# RoBeast_uC.net
KiCad netlist of a schematic drawn in Altium Designer
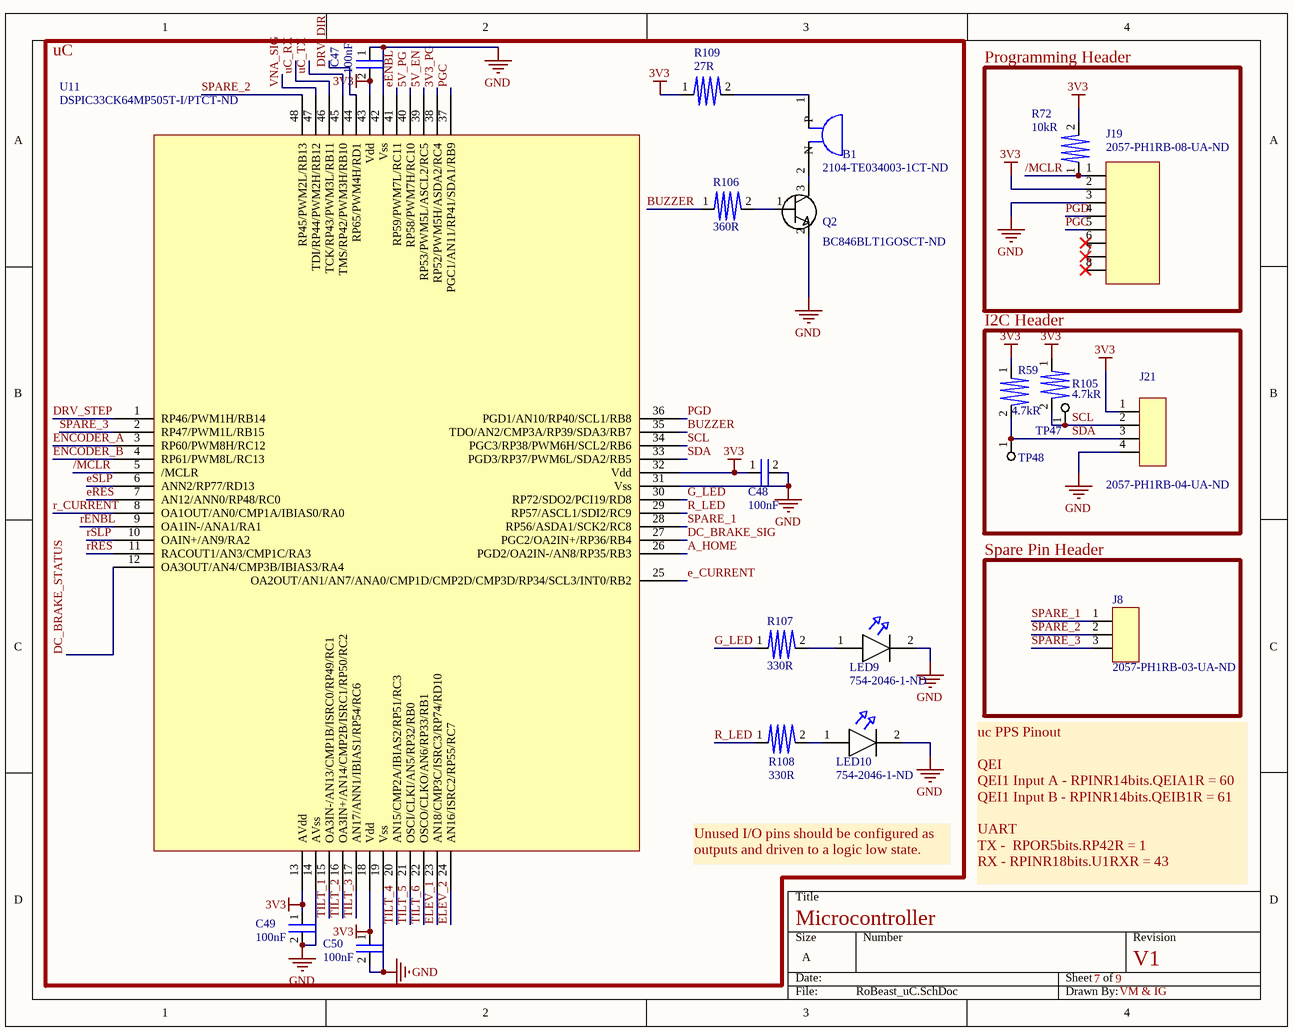
[diagram p0: RoBeast_uC.SchDoc]

(export (version "E")
  (design (tool "Eeschema 10.0.6"))
  (components
    (comp (ref "B1")
      (value "Buzzer")
      (footprint "TE034003-1")
      (description "Electro-mechanical Transducer")
      (fields
        (field (name "MANUFACTURER") "DB Unlimited")
        (field (name "MANUFACTURER PART NUMBER") "TE034003-1")
        (field (name "SUPPLIER PART NUMBER 1") "2104-TE034003-1CT-ND")
      )
      (libsource (lib "RoBeast_Schematic_Library") (part "TE034003-1"))
    )
    (comp (ref "C47")
      (value "100nF")
      (footprint "0805")
      (fields
        (field (name "MANUFACTURER") "KEMET")
        (field (name "MANUFACTURER PART NUMBER") "C0805C104J5RACTU")
      )
      (libsource (lib "RoBeast_Schematic_Library") (part "C0805C104J5RAC7800"))
    )
    (comp (ref "C48")
      (value "100nF")
      (footprint "0805")
      (fields
        (field (name "MANUFACTURER") "KEMET")
        (field (name "MANUFACTURER PART NUMBER") "C0805C104J5RACTU")
      )
      (libsource (lib "RoBeast_Schematic_Library") (part "C0805C104J5RAC7800"))
    )
    (comp (ref "C49")
      (value "100nF")
      (footprint "0805")
      (fields
        (field (name "MANUFACTURER") "KEMET")
        (field (name "MANUFACTURER PART NUMBER") "C0805C104J5RACTU")
      )
      (libsource (lib "RoBeast_Schematic_Library") (part "C0805C104J5RAC7800"))
    )
    (comp (ref "C50")
      (value "100nF")
      (footprint "0805")
      (fields
        (field (name "MANUFACTURER") "KEMET")
        (field (name "MANUFACTURER PART NUMBER") "C0805C104J5RACTU")
      )
      (libsource (lib "RoBeast_Schematic_Library") (part "C0805C104J5RAC7800"))
    )
    (comp (ref "J8")
      (value "3 Pin Connector")
      (footprint "PH1RB-03-UA")
      (description "Conn Unshrouded Header HDR 3 POS 2.54mm Solder RA Side Entry Thru-Hole")
      (fields
        (field (name "MANUFACTURER") "Adam Equipment")
        (field (name "MANUFACTURER PART NUMBER") "PH1RB-03-UA")
        (field (name "SUPPLIER PART NUMBER") "2057-PH1RB-03-UA-ND")
      )
      (libsource (lib "RoBeast_Schematic_Library") (part "PH1RB-03-UA"))
    )
    (comp (ref "J19")
      (value "8 Pin Connector")
      (footprint "PH1RB-08-UA")
      (description "Conn Unshrouded Header HDR 8 POS 2.54mm Solder RA Thru-Hole")
      (fields
        (field (name "MANUFACTURER") "Adam Equipment")
        (field (name "MANUFACTURER PART NUMBER") "PH1RB-08-UA")
        (field (name "SUPPLIER PART NUMBER 1") "2057-PH1RB-08-UA-ND")
      )
      (libsource (lib "RoBeast_Schematic_Library") (part "PH1RB-08-UA"))
    )
    (comp (ref "J21")
      (value "4 Pin Connector")
      (footprint "PH1RB-04-UA")
      (description "Conn Unshrouded Header HDR 4 POS 2.54mm Solder RA Thru-Hole")
      (fields
        (field (name "MANUFACTURER") "Adam Equipment")
        (field (name "MANUFACTURER PART NUMBER") "PH1RB-04-UA")
        (field (name "SUPPLIER PART NUMBER") "2057-PH1RB-04-UA-ND")
      )
      (libsource (lib "RoBeast_Schematic_Library") (part "PH1RB-04-UA"))
    )
    (comp (ref "LED9")
      (value "Blue LED")
      (footprint "0805_LED")
      (description "Single Color LED")
      (fields
        (field (name "MANUFACTURER") "Kingbright")
        (field (name "MANUFACTURER PART NUMBER") "APTD2012LQBC/D")
        (field (name "SUPPLIER PART NUMBER 1") "754-2046-1-ND")
      )
      (libsource (lib "RoBeast_Schematic_Library") (part "APTD2012LQBC/D"))
    )
    (comp (ref "LED10")
      (value "Blue LED")
      (footprint "0805_LED")
      (description "Single Color LED")
      (fields
        (field (name "MANUFACTURER") "Kingbright")
        (field (name "MANUFACTURER PART NUMBER") "APTD2012LQBC/D")
        (field (name "SUPPLIER PART NUMBER 1") "754-2046-1-ND")
      )
      (libsource (lib "RoBeast_Schematic_Library") (part "APTD2012LQBC/D"))
    )
    (comp (ref "Q2")
      (value "NPN BJT")
      (footprint "BC846BLT1G")
      (description "Small Signal Bipolar Transistor, 0.1A I(C), 65V V(BR)CEO, 1-Element, NPN, Silicon, TO-236")
      (fields
        (field (name "MANUFACTURER") "ON Semiconductor")
        (field (name "MANUFACTURER PART NUMBER") "BC846BLT1G")
        (field (name "SUPPLIER PART NUMBER 1") "BC846BLT1GOSCT-ND")
      )
      (libsource (lib "RoBeast_Schematic_Library") (part "BC846BLT1G"))
    )
    (comp (ref "R59")
      (value "4.7kR")
      (footprint "0805")
      (fields
        (field (name "MANUFACTURER") "Vishay Dale")
        (field (name "MANUFACTURER PART NUMBER") "RCC08054K70FKEA")
      )
      (libsource (lib "RoBeast_Schematic_Library") (part "RCC08054K70FKEA"))
    )
    (comp (ref "R72")
      (value "10kR")
      (footprint "0805")
      (fields
        (field (name "MANUFACTURER") "Stackpole Electronics")
        (field (name "MANUFACTURER PART NUMBER") "RMCF0805FT10K0")
        (field (name "TOLERANCE") "1%")
      )
      (libsource (lib "RoBeast_Schematic_Library") (part "RMCF0805FT10K0"))
    )
    (comp (ref "R105")
      (value "4.7kR")
      (footprint "0805")
      (fields
        (field (name "MANUFACTURER") "Vishay Dale")
        (field (name "MANUFACTURER PART NUMBER") "RCC08054K70FKEA")
      )
      (libsource (lib "RoBeast_Schematic_Library") (part "RCC08054K70FKEA"))
    )
    (comp (ref "R106")
      (value "360R")
      (footprint "0805")
      (fields
        (field (name "MANUFACTURER") "Yageo")
        (field (name "MANUFACTURER PART NUMBER") "RC0805FR-07360RL")
        (field (name "TOLERANCE") "1%")
      )
      (libsource (lib "RoBeast_Schematic_Library") (part "RC0805FR-07360RL"))
    )
    (comp (ref "R107")
      (value "330R")
      (footprint "0805")
      (fields
        (field (name "MANUFACTURER") "Yageo")
        (field (name "MANUFACTURER PART NUMBER") "RC0805FR-13330RL")
        (field (name "TOLERANCE") "1%")
      )
      (libsource (lib "RoBeast_Schematic_Library") (part "RC0805FR-13330RL"))
    )
    (comp (ref "R108")
      (value "330R")
      (footprint "0805")
      (fields
        (field (name "MANUFACTURER") "Yageo")
        (field (name "MANUFACTURER PART NUMBER") "RC0805FR-13330RL")
        (field (name "TOLERANCE") "1%")
      )
      (libsource (lib "RoBeast_Schematic_Library") (part "RC0805FR-13330RL"))
    )
    (comp (ref "R109")
      (value "27R")
      (footprint "0805")
      (fields
        (field (name "MANUFACTURER") "KOA Speer")
        (field (name "MANUFACTURER PART NUMBER") "SG73P2ATTD27R0F")
        (field (name "TOLERANCE") "1%")
      )
      (libsource (lib "RoBeast_Schematic_Library") (part "SG73P2ATTD27R0F"))
    )
    (comp (ref "TP47")
      (value "Test Point")
      (footprint "RCWCTE")
      (description "Testing/Accessories")
      (fields (field (name "MANUFACTURER") "KOA Speer") (field (name "MANUFACTURER PART NUMBER") "RCWCTE"))
      (libsource (lib "RoBeast_Schematic_Library") (part "RCWCTE"))
    )
    (comp (ref "TP48")
      (value "Test Point")
      (footprint "RCWCTE")
      (description "Testing/Accessories")
      (fields (field (name "MANUFACTURER") "KOA Speer") (field (name "MANUFACTURER PART NUMBER") "RCWCTE"))
      (libsource (lib "RoBeast_Schematic_Library") (part "RCWCTE"))
    )
    (comp (ref "U11")
      (value "uC")
      (footprint "DSPIC33CK64MP505T-I/PT")
      (description "16-Bit Size, 0-Ext Bit, 64MHz, CMOS, PQFP48")
      (fields
        (field (name "MANUFACTURER") "Microchip")
        (field (name "MANUFACTURER PART NUMBER") "DSPIC33CK64MP505T-I/PT")
        (field (name "SUPPLIER PART NUMBER") "DSPIC33CK64MP505T-I/PTCT-ND")
      )
      (libsource (lib "RoBeast_Schematic_Library") (part "DSPIC33CK64MP505T-I/PT"))
    )
  )
  (nets
    (net (code "1") (name "/3V3_PG") (class "Default")
      (node (ref "U11") (pin "38") (pinfunction "RP52/PWM5H/ASDA2/RC4_38") (pintype "passive"))
    )
    (net (code "2") (name "/5V_EN") (class "Default")
      (node (ref "U11") (pin "39") (pinfunction "RP53/PWM5L/ASCL2/RC5_39") (pintype "passive"))
    )
    (net (code "3") (name "/5V_PG") (class "Default")
      (node (ref "U11") (pin "40") (pinfunction "RP58/PWM7H/RC10_40") (pintype "passive"))
    )
    (net (code "4") (name "/A_HOME") (class "Default")
      (node (ref "U11") (pin "26") (pinfunction "PGD2/OA2IN-/AN8/RP35/RB3_26") (pintype "passive"))
    )
    (net (code "5") (name "/BUZZER") (class "Default")
      (node (ref "R106") (pin "1") (pinfunction "1_1") (pintype "passive"))
      (node (ref "U11") (pin "35") (pinfunction "TDO/AN2/CMP3A/RP39/SDA3/RB7_35") (pintype "passive"))
    )
    (net (code "6") (name "/DC_BRAKE_SIG") (class "Default")
      (node (ref "U11") (pin "27") (pinfunction "PGC2/OA2IN+/RP36/RB4_27") (pintype "passive"))
    )
    (net (code "7") (name "/DC_BRAKE_STATUS") (class "Default")
      (node (ref "U11") (pin "12") (pinfunction "OA3OUT/AN4/CMP3B/IBIAS3/RA4_12") (pintype "passive"))
    )
    (net (code "8") (name "/DRV_DIR") (class "Default")
      (node (ref "U11") (pin "44") (pinfunction "RP65/PWM4H/RD1_44") (pintype "passive"))
    )
    (net (code "9") (name "/DRV_STEP") (class "Default")
      (node (ref "U11") (pin "1") (pinfunction "RP46/PWM1H/RB14_1") (pintype "passive"))
    )
    (net (code "10") (name "/ELEV_1") (class "Default")
      (node (ref "U11") (pin "23") (pinfunction "AN18/CMP3C/ISRC3/RP74/RD10_23") (pintype "passive"))
    )
    (net (code "11") (name "/ELEV_2") (class "Default")
      (node (ref "U11") (pin "24") (pinfunction "AN16/ISRC2/RP55/RC7_24") (pintype "passive"))
    )
    (net (code "12") (name "/ENCODER_A") (class "Default")
      (node (ref "U11") (pin "3") (pinfunction "RP60/PWM8H/RC12_3") (pintype "passive"))
    )
    (net (code "13") (name "/ENCODER_B") (class "Default")
      (node (ref "U11") (pin "4") (pinfunction "RP61/PWM8L/RC13_4") (pintype "passive"))
    )
    (net (code "14") (name "/G_LED") (class "Default")
      (node (ref "R107") (pin "1") (pinfunction "1_1") (pintype "passive"))
      (node (ref "U11") (pin "30") (pinfunction "RP72/SDO2/PCI19/RD8_30") (pintype "passive"))
    )
    (net (code "15") (name "/PGC") (class "Default")
      (node (ref "J19") (pin "5") (pinfunction "5_5") (pintype "passive"))
      (node (ref "U11") (pin "37") (pinfunction "PGC1/AN11/RP41/SDA1/RB9_37") (pintype "passive"))
    )
    (net (code "16") (name "/PGD") (class "Default")
      (node (ref "J19") (pin "4") (pinfunction "4_4") (pintype "passive"))
      (node (ref "U11") (pin "36") (pinfunction "PGD1/AN10/RP40/SCL1/RB8_36") (pintype "passive"))
    )
    (net (code "17") (name "/R_LED") (class "Default")
      (node (ref "R108") (pin "1") (pinfunction "1_1") (pintype "passive"))
      (node (ref "U11") (pin "29") (pinfunction "RP57/ASCL1/SDI2/RC9_29") (pintype "passive"))
    )
    (net (code "18") (name "/SCL") (class "Default")
      (node (ref "J21") (pin "2") (pinfunction "2_2") (pintype "passive"))
      (node (ref "R105") (pin "2") (pinfunction "2_2") (pintype "passive"))
      (node (ref "TP47") (pin "1") (pinfunction "1_1") (pintype "passive"))
      (node (ref "U11") (pin "34") (pinfunction "PGC3/RP38/PWM6H/SCL2/RB6_34") (pintype "passive"))
    )
    (net (code "19") (name "/SDA") (class "Default")
      (node (ref "J21") (pin "3") (pinfunction "3_3") (pintype "passive"))
      (node (ref "R59") (pin "2") (pinfunction "2_2") (pintype "passive"))
      (node (ref "TP48") (pin "1") (pinfunction "1_1") (pintype "passive"))
      (node (ref "U11") (pin "33") (pinfunction "PGD3/RP37/PWM6L/SDA2/RB5_33") (pintype "passive"))
    )
    (net (code "20") (name "/SPARE_1") (class "Default")
      (node (ref "J8") (pin "1") (pinfunction "1_1") (pintype "passive"))
      (node (ref "U11") (pin "28") (pinfunction "RP56/ASDA1/SCK2/RC8_28") (pintype "passive"))
    )
    (net (code "21") (name "/SPARE_2") (class "Default")
      (node (ref "J8") (pin "2") (pinfunction "2_2") (pintype "passive"))
      (node (ref "U11") (pin "48") (pinfunction "RP45/PWM2L/RB13_48") (pintype "passive"))
    )
    (net (code "22") (name "/SPARE_3") (class "Default")
      (node (ref "J8") (pin "3") (pinfunction "3_3") (pintype "passive"))
      (node (ref "U11") (pin "2") (pinfunction "RP47/PWM1L/RB15_2") (pintype "passive"))
    )
    (net (code "23") (name "/TILT_1") (class "Default")
      (node (ref "U11") (pin "15") (pinfunction "OA3IN-/AN13/CMP1B/ISRC0/RP49/RC1_15") (pintype "passive"))
    )
    (net (code "24") (name "/TILT_2") (class "Default")
      (node (ref "U11") (pin "16") (pinfunction "OA3IN+/AN14/CMP2B/ISRC1/RP50/RC2_16") (pintype "passive"))
    )
    (net (code "25") (name "/TILT_3") (class "Default")
      (node (ref "U11") (pin "17") (pinfunction "AN17/ANN1/IBIAS1/RP54/RC6_17") (pintype "passive"))
    )
    (net (code "26") (name "/TILT_4") (class "Default")
      (node (ref "U11") (pin "20") (pinfunction "AN15/CMP2A/IBIAS2/RP51/RC3_20") (pintype "passive"))
    )
    (net (code "27") (name "/TILT_5") (class "Default")
      (node (ref "U11") (pin "21") (pinfunction "OSCI/CLKI/AN5/RP32/RB0_21") (pintype "passive"))
    )
    (net (code "28") (name "/TILT_6") (class "Default")
      (node (ref "U11") (pin "22") (pinfunction "OSCO/CLKO/AN6/RP33/RB1_22") (pintype "passive"))
    )
    (net (code "29") (name "/VNA_SIG") (class "Default")
      (node (ref "U11") (pin "47") (pinfunction "TDI/RP44/PWM2H/RB12_47") (pintype "passive"))
    )
    (net (code "30") (name "/eENBL") (class "Default")
      (node (ref "U11") (pin "41") (pinfunction "RP59/PWM7L/RC11_41") (pintype "passive"))
    )
    (net (code "31") (name "/eRES") (class "Default")
      (node (ref "U11") (pin "7") (pinfunction "AN12/ANN0/RP48/RC0_7") (pintype "passive"))
    )
    (net (code "32") (name "/eSLP") (class "Default")
      (node (ref "U11") (pin "6") (pinfunction "ANN2/RP77/RD13_6") (pintype "passive"))
    )
    (net (code "33") (name "/e_CURRENT") (class "Default")
      (node (ref "U11") (pin "25") (pinfunction "OA2OUT/AN1/AN7/ANA0/CMP1D/CMP2D/CMP3D/RP34/SCL3/INT0/RB2_25") (pintype "passive"))
    )
    (net (code "34") (name "/rENBL") (class "Default")
      (node (ref "U11") (pin "9") (pinfunction "OA1IN-/ANA1/RA1_9") (pintype "passive"))
    )
    (net (code "35") (name "/rRES") (class "Default")
      (node (ref "U11") (pin "11") (pinfunction "RACOUT1/AN3/CMP1C/RA3_11") (pintype "passive"))
    )
    (net (code "36") (name "/rSLP") (class "Default")
      (node (ref "U11") (pin "10") (pinfunction "OAIN+/AN9/RA2_10") (pintype "passive"))
    )
    (net (code "37") (name "/r_CURRENT") (class "Default")
      (node (ref "U11") (pin "8") (pinfunction "OA1OUT/AN0/CMP1A/IBIAS0/RA0_8") (pintype "passive"))
    )
    (net (code "38") (name "/uC_RX") (class "Default")
      (node (ref "U11") (pin "46") (pinfunction "TCK/RP43/PWM3L/RB11_46") (pintype "passive"))
    )
    (net (code "39") (name "/uC_TX") (class "Default")
      (node (ref "U11") (pin "45") (pinfunction "TMS/RP42/PWM3H/RB10_45") (pintype "passive"))
    )
    (net (code "40") (name "/{slash}MCLR") (class "Default")
      (node (ref "J19") (pin "1") (pinfunction "1_1") (pintype "passive"))
      (node (ref "R72") (pin "1") (pinfunction "1_1") (pintype "passive"))
      (node (ref "U11") (pin "5") (pinfunction "/MCLR_5") (pintype "passive"))
    )
    (net (code "41") (name "3V3") (class "Default")
      (node (ref "C47") (pin "2") (pinfunction "2_2") (pintype "passive"))
      (node (ref "C48") (pin "1") (pinfunction "1_1") (pintype "passive"))
      (node (ref "C49") (pin "1") (pinfunction "1_1") (pintype "passive"))
      (node (ref "C50") (pin "1") (pinfunction "1_1") (pintype "passive"))
      (node (ref "J19") (pin "2") (pinfunction "2_2") (pintype "passive"))
      (node (ref "J21") (pin "1") (pinfunction "1_1") (pintype "passive"))
      (node (ref "R105") (pin "1") (pinfunction "1_1") (pintype "passive"))
      (node (ref "R109") (pin "1") (pinfunction "1_1") (pintype "passive"))
      (node (ref "R59") (pin "1") (pinfunction "1_1") (pintype "passive"))
      (node (ref "R72") (pin "2") (pinfunction "2_2") (pintype "passive"))
      (node (ref "U11") (pin "13") (pinfunction "AVdd_13") (pintype "passive"))
      (node (ref "U11") (pin "18") (pinfunction "Vdd_18") (pintype "passive"))
      (node (ref "U11") (pin "32") (pinfunction "Vdd_32") (pintype "passive"))
      (node (ref "U11") (pin "43") (pinfunction "Vdd_43") (pintype "passive"))
    )
    (net (code "42") (name "GND") (class "Default")
      (node (ref "C47") (pin "1") (pinfunction "1_1") (pintype "passive"))
      (node (ref "C48") (pin "2") (pinfunction "2_2") (pintype "passive"))
      (node (ref "C49") (pin "2") (pinfunction "2_2") (pintype "passive"))
      (node (ref "C50") (pin "2") (pinfunction "2_2") (pintype "passive"))
      (node (ref "J19") (pin "3") (pinfunction "3_3") (pintype "passive"))
      (node (ref "J21") (pin "4") (pinfunction "4_4") (pintype "passive"))
      (node (ref "LED10") (pin "2") (pinfunction "K_2") (pintype "passive"))
      (node (ref "LED9") (pin "2") (pinfunction "K_2") (pintype "passive"))
      (node (ref "Q2") (pin "2") (pinfunction "E_2") (pintype "passive"))
      (node (ref "U11") (pin "14") (pinfunction "AVss_14") (pintype "passive"))
      (node (ref "U11") (pin "19") (pinfunction "Vss_19") (pintype "passive"))
      (node (ref "U11") (pin "31") (pinfunction "Vss_31") (pintype "passive"))
      (node (ref "U11") (pin "42") (pinfunction "Vss_42") (pintype "passive"))
    )
    (net (code "43") (name "Net-(B1-N)") (class "Default")
      (node (ref "B1") (pin "2") (pinfunction "N_2") (pintype "passive"))
      (node (ref "Q2") (pin "3") (pinfunction "C_3") (pintype "passive"))
    )
    (net (code "44") (name "Net-(B1-P)") (class "Default")
      (node (ref "B1") (pin "1") (pinfunction "P_1") (pintype "passive"))
      (node (ref "R109") (pin "2") (pinfunction "2_2") (pintype "passive"))
    )
    (net (code "45") (name "Net-(LED9-A)") (class "Default")
      (node (ref "LED9") (pin "1") (pinfunction "A_1") (pintype "passive"))
      (node (ref "R107") (pin "2") (pinfunction "2_2") (pintype "passive"))
    )
    (net (code "46") (name "Net-(LED10-A)") (class "Default")
      (node (ref "LED10") (pin "1") (pinfunction "A_1") (pintype "passive"))
      (node (ref "R108") (pin "2") (pinfunction "2_2") (pintype "passive"))
    )
    (net (code "47") (name "Net-(Q2-B)") (class "Default")
      (node (ref "Q2") (pin "1") (pinfunction "B_1") (pintype "passive"))
      (node (ref "R106") (pin "2") (pinfunction "2_2") (pintype "passive"))
    )
    (net (code "48") (name "unconnected-(J19-Pad6)") (class "Default")
      (node (ref "J19") (pin "6") (pinfunction "6_6") (pintype "passive+no_connect"))
    )
    (net (code "49") (name "unconnected-(J19-Pad7)") (class "Default")
      (node (ref "J19") (pin "7") (pinfunction "7_7") (pintype "passive+no_connect"))
    )
    (net (code "50") (name "unconnected-(J19-Pad8)") (class "Default")
      (node (ref "J19") (pin "8") (pinfunction "8_8") (pintype "passive+no_connect"))
    )
  )
)
